# SCH.net
KiCad netlist of a schematic drawn in EasyEDA
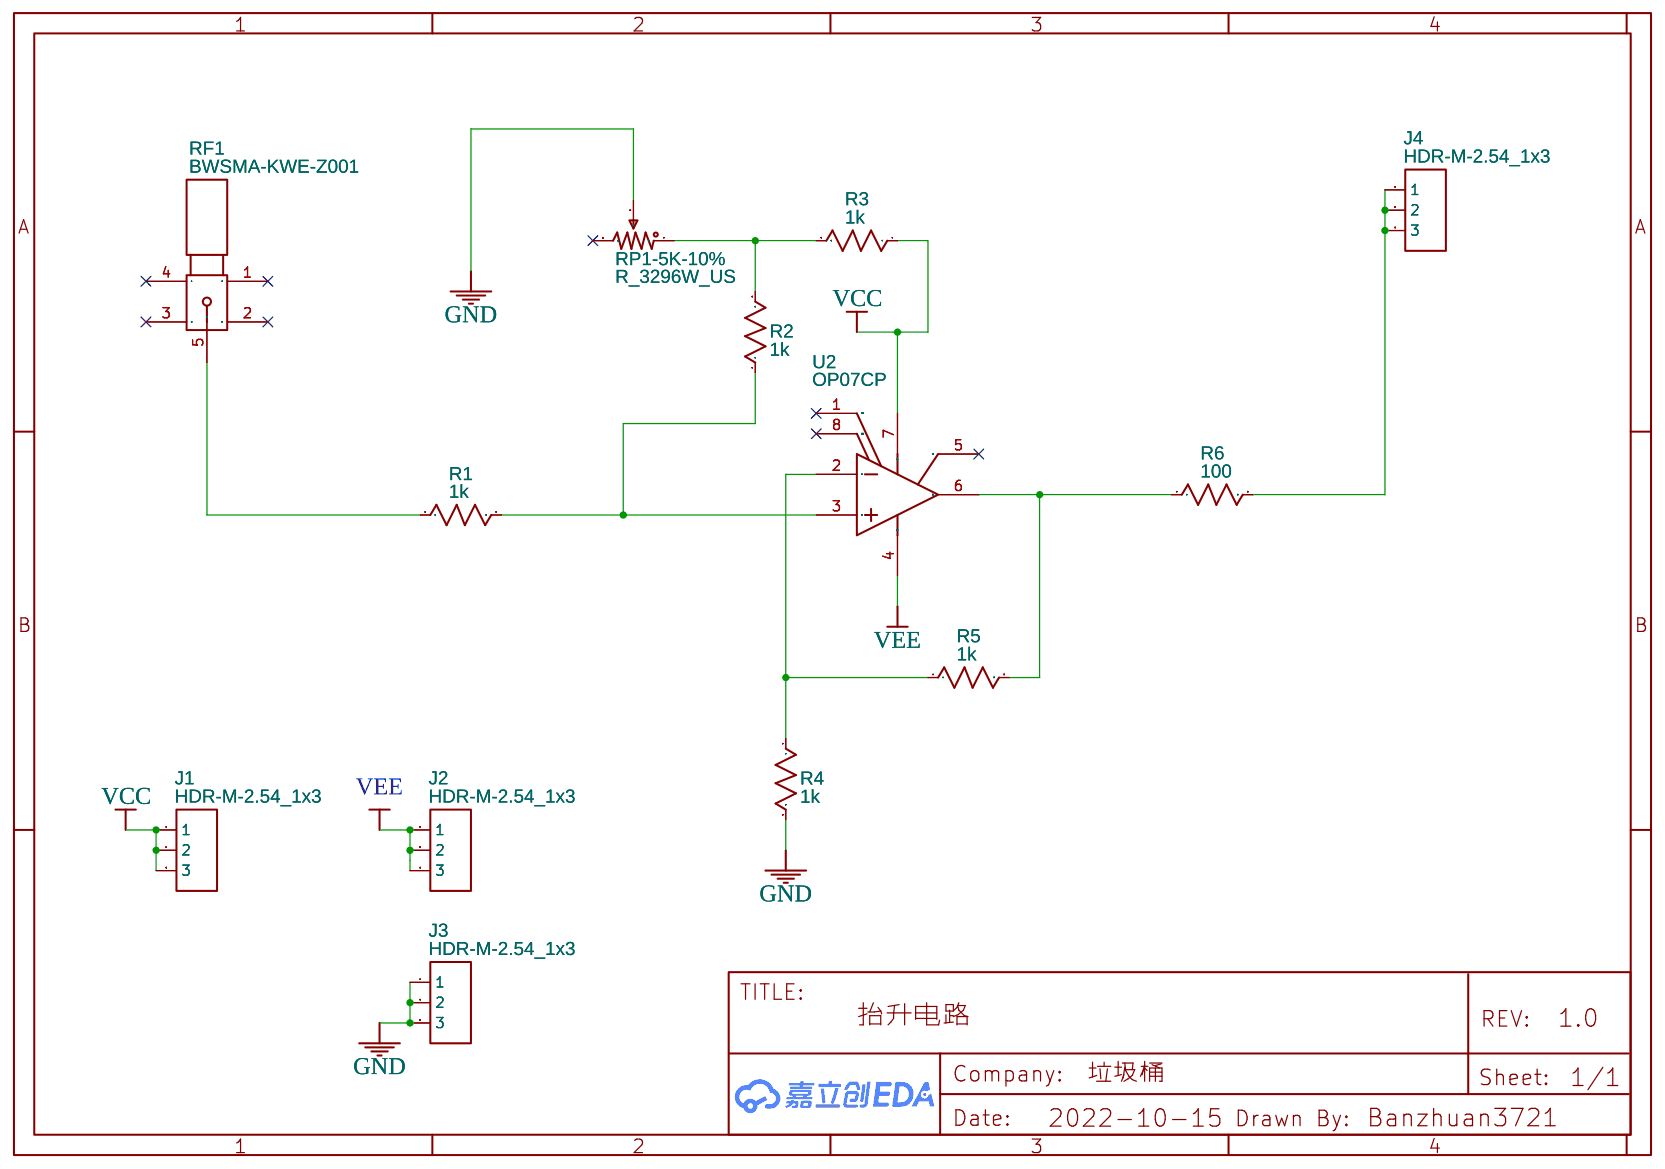
[diagram p0: schematic sheet]

(export (version "E")
  (design (tool "Eeschema 10.0.6"))
  (components
    (comp (ref "J1")
      (value "HDR-M-2.54_1x3")
      (fields (field (name "BOM_Supplier Part") "C180248"))
      (libsource (lib "") (part "HDR-M-2.54_1x3"))
    )
    (comp (ref "J2")
      (value "HDR-M-2.54_1x3")
      (fields (field (name "BOM_Supplier Part") "C180248"))
      (libsource (lib "") (part "HDR-M-2.54_1x3"))
    )
    (comp (ref "J3")
      (value "HDR-M-2.54_1x3")
      (fields (field (name "BOM_Supplier Part") "C180248"))
      (libsource (lib "") (part "HDR-M-2.54_1x3"))
    )
    (comp (ref "J4")
      (value "HDR-M-2.54_1x3")
      (fields (field (name "BOM_Supplier Part") "C180248"))
      (libsource (lib "") (part "HDR-M-2.54_1x3"))
    )
    (comp (ref "R1") (value "1k") (libsource (lib "") (part "R_AXIAL-0.3_US")))
    (comp (ref "R2") (value "1k") (libsource (lib "") (part "R_AXIAL-0.3_US_2")))
    (comp (ref "R3") (value "1k") (libsource (lib "") (part "R_AXIAL-0.3_US_3")))
    (comp (ref "R4") (value "1k") (libsource (lib "") (part "R_AXIAL-0.3_US_1")))
    (comp (ref "R5") (value "1k") (libsource (lib "") (part "R_AXIAL-0.3_US")))
    (comp (ref "R6") (value "100") (libsource (lib "") (part "R_AXIAL-0.3_US")))
    (comp (ref "RF1")
      (value "BWSMA-KWE-Z001")
      (fields (field (name "BOM_Supplier Part") "C496551"))
      (libsource (lib "") (part "BWSMA-KWE-Z001"))
    )
    (comp (ref "RP1-5K-10%") (value "R_3296W_US") (libsource (lib "") (part "R_3296W_US")))
    (comp (ref "U2")
      (value "OP07CP")
      (fields (field (name "BOM_Supplier Part") "C5224"))
      (libsource (lib "") (part "OP07CP"))
    )
  )
  (nets
    (net (code "1") (name "GND") (class "Default")
      (node (ref "J3") (pin "1") (pinfunction "1_1") (pintype "input"))
      (node (ref "J3") (pin "2") (pinfunction "2_2") (pintype "input"))
      (node (ref "J3") (pin "3") (pinfunction "3_3") (pintype "input"))
      (node (ref "R4") (pin "2") (pinfunction "2_2") (pintype "unspecified"))
      (node (ref "RP1-5K-10%") (pin "2") (pinfunction "2_2") (pintype "unspecified"))
    )
    (net (code "2") (name "Net-(J4-Pad1)") (class "Default")
      (node (ref "J4") (pin "1") (pinfunction "1_1") (pintype "input"))
      (node (ref "J4") (pin "2") (pinfunction "2_2") (pintype "input"))
      (node (ref "J4") (pin "3") (pinfunction "3_3") (pintype "input"))
      (node (ref "R6") (pin "2") (pinfunction "2_2") (pintype "unspecified"))
    )
    (net (code "3") (name "Net-(R1-Pad1)") (class "Default")
      (node (ref "R1") (pin "1") (pinfunction "1_1") (pintype "unspecified"))
      (node (ref "RF1") (pin "5") (pinfunction "5_5") (pintype "unspecified"))
    )
    (net (code "4") (name "Net-(R2-Pad2)") (class "Default")
      (node (ref "R2") (pin "2") (pinfunction "2_2") (pintype "unspecified"))
      (node (ref "R3") (pin "2") (pinfunction "2_2") (pintype "unspecified"))
      (node (ref "RP1-5K-10%") (pin "1") (pinfunction "1_1") (pintype "unspecified"))
    )
    (net (code "5") (name "Net-(U2-IN+)") (class "Default")
      (node (ref "R1") (pin "2") (pinfunction "2_2") (pintype "unspecified"))
      (node (ref "R2") (pin "1") (pinfunction "1_1") (pintype "unspecified"))
      (node (ref "U2") (pin "3") (pinfunction "IN+_3") (pintype "unspecified"))
    )
    (net (code "6") (name "Net-(U2-IN-)") (class "Default")
      (node (ref "R4") (pin "1") (pinfunction "1_1") (pintype "unspecified"))
      (node (ref "R5") (pin "1") (pinfunction "1_1") (pintype "unspecified"))
      (node (ref "U2") (pin "2") (pinfunction "IN-_2") (pintype "unspecified"))
    )
    (net (code "7") (name "Net-(U2-OUT)") (class "Default")
      (node (ref "R5") (pin "2") (pinfunction "2_2") (pintype "unspecified"))
      (node (ref "R6") (pin "1") (pinfunction "1_1") (pintype "unspecified"))
      (node (ref "U2") (pin "6") (pinfunction "OUT_6") (pintype "output"))
    )
    (net (code "8") (name "VCC") (class "Default")
      (node (ref "J1") (pin "1") (pinfunction "1_1") (pintype "input"))
      (node (ref "J1") (pin "2") (pinfunction "2_2") (pintype "input"))
      (node (ref "J1") (pin "3") (pinfunction "3_3") (pintype "input"))
      (node (ref "R3") (pin "1") (pinfunction "1_1") (pintype "unspecified"))
      (node (ref "U2") (pin "7") (pinfunction "VCC+_7") (pintype "passive"))
    )
    (net (code "9") (name "VEE") (class "Default")
      (node (ref "J2") (pin "1") (pinfunction "1_1") (pintype "input"))
      (node (ref "J2") (pin "2") (pinfunction "2_2") (pintype "input"))
      (node (ref "J2") (pin "3") (pinfunction "3_3") (pintype "input"))
      (node (ref "U2") (pin "4") (pinfunction "VCC-_4") (pintype "passive"))
    )
    (net (code "10") (name "unconnected-(RF1-Pad1)") (class "Default")
      (node (ref "RF1") (pin "1") (pinfunction "1_1") (pintype "unspecified+no_connect"))
    )
    (net (code "11") (name "unconnected-(RF1-Pad2)") (class "Default")
      (node (ref "RF1") (pin "2") (pinfunction "2_2") (pintype "unspecified+no_connect"))
    )
    (net (code "12") (name "unconnected-(RF1-Pad3)") (class "Default")
      (node (ref "RF1") (pin "3") (pinfunction "3_3") (pintype "unspecified+no_connect"))
    )
    (net (code "13") (name "unconnected-(RF1-Pad4)") (class "Default")
      (node (ref "RF1") (pin "4") (pinfunction "4_4") (pintype "unspecified+no_connect"))
    )
    (net (code "14") (name "unconnected-(RP1-5K-10%-Pad3)") (class "Default")
      (node (ref "RP1-5K-10%") (pin "3") (pinfunction "3_3") (pintype "unspecified+no_connect"))
    )
    (net (code "15") (name "unconnected-(U2-NC-Pad5)") (class "Default")
      (node (ref "U2") (pin "5") (pinfunction "NC_5") (pintype "unspecified+no_connect"))
    )
    (net (code "16") (name "unconnected-(U2-OFFSET_N1-Pad1)") (class "Default")
      (node (ref "U2") (pin "1") (pinfunction "OFFSET_N1_1") (pintype "unspecified+no_connect"))
    )
    (net (code "17") (name "unconnected-(U2-OFFSET_N2-Pad8)") (class "Default")
      (node (ref "U2") (pin "8") (pinfunction "OFFSET_N2_8") (pintype "unspecified+no_connect"))
    )
  )
)
